# MAXIM-ADC3.net
KiCad netlist of a schematic drawn in Altium Designer
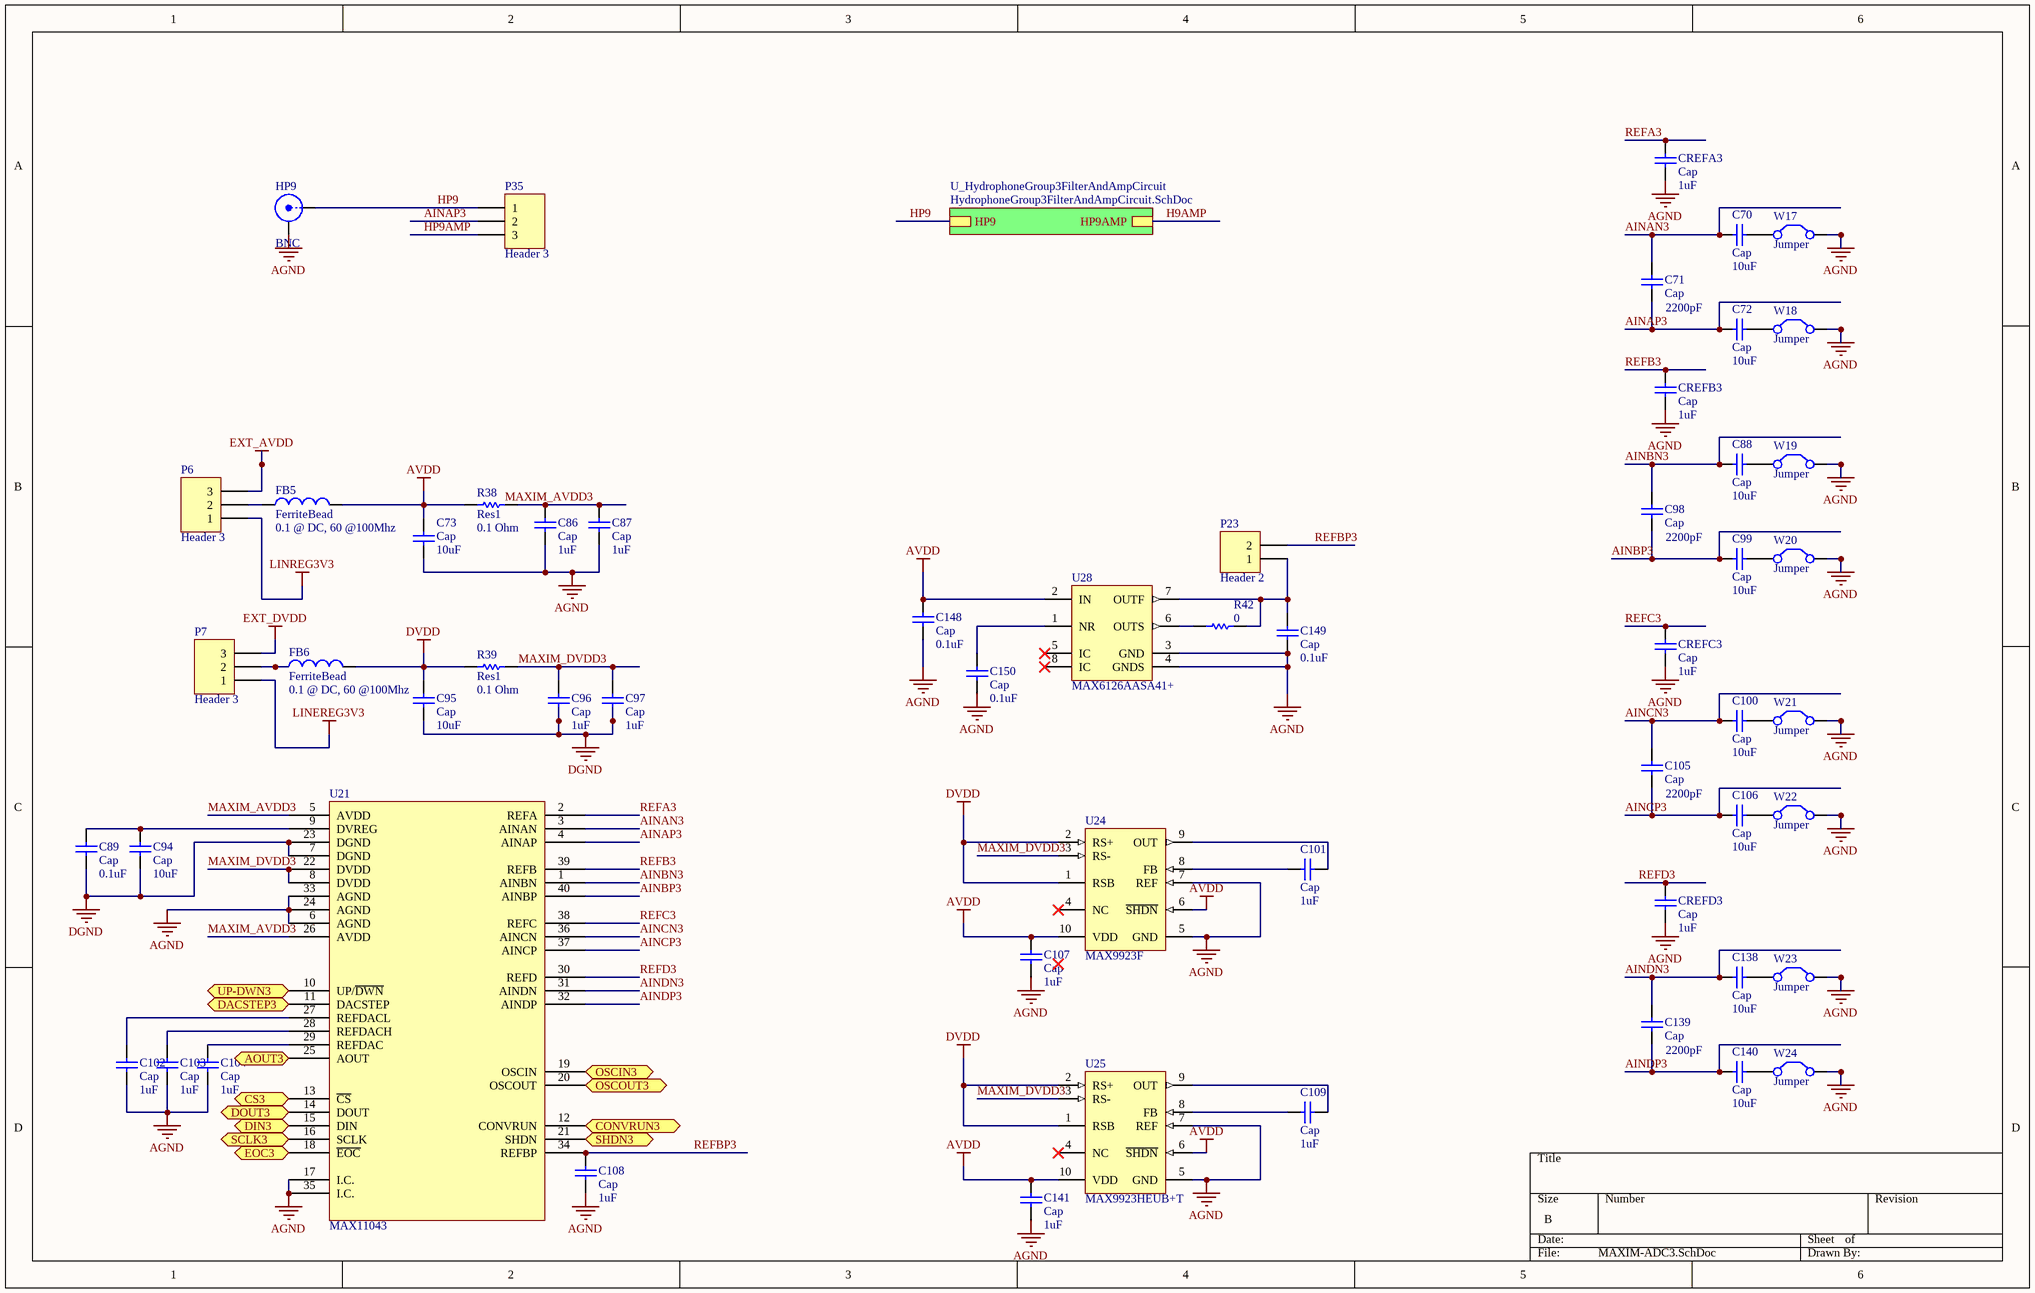
[diagram p0: MAXIM-ADC3.SchDoc]

(export (version "E")
  (design (tool "Eeschema 10.0.6"))
  (components
    (comp (ref "C70")
      (value "Cap")
      (footprint "RAD-0.3")
      (description "Capacitor")
      (fields (field (name "ALTIUM_VALUE") "10uF") (field (name "PUBLISHER") "Altium Limited"))
      (libsource (lib "Miscellaneous Devices") (part "Cap"))
    )
    (comp (ref "C71")
      (value "Cap")
      (footprint "RAD-0.3")
      (description "Capacitor")
      (fields (field (name "ALTIUM_VALUE") "2200pF") (field (name "PUBLISHER") "Altium Limited"))
      (libsource (lib "Miscellaneous Devices") (part "Cap"))
    )
    (comp (ref "C72")
      (value "Cap")
      (footprint "RAD-0.3")
      (description "Capacitor")
      (fields (field (name "ALTIUM_VALUE") "10uF") (field (name "PUBLISHER") "Altium Limited"))
      (libsource (lib "Miscellaneous Devices") (part "Cap"))
    )
    (comp (ref "C73")
      (value "Cap")
      (footprint "RAD-0.3")
      (description "Capacitor")
      (fields (field (name "ALTIUM_VALUE") "10uF") (field (name "PUBLISHER") "Altium Limited"))
      (libsource (lib "Miscellaneous Devices") (part "Cap"))
    )
    (comp (ref "C86")
      (value "Cap")
      (footprint "0603")
      (description "Capacitor")
      (fields (field (name "ALTIUM_VALUE") "1uF") (field (name "PUBLISHER") "Altium Limited"))
      (libsource (lib "Miscellaneous Devices") (part "Cap"))
    )
    (comp (ref "C87")
      (value "Cap")
      (footprint "RAD-0.3")
      (description "Capacitor")
      (fields (field (name "ALTIUM_VALUE") "1uF") (field (name "PUBLISHER") "Altium Limited"))
      (libsource (lib "Miscellaneous Devices") (part "Cap"))
    )
    (comp (ref "C88")
      (value "Cap")
      (footprint "RAD-0.3")
      (description "Capacitor")
      (fields (field (name "ALTIUM_VALUE") "10uF") (field (name "PUBLISHER") "Altium Limited"))
      (libsource (lib "Miscellaneous Devices") (part "Cap"))
    )
    (comp (ref "C89")
      (value "Cap")
      (footprint "RAD-0.3")
      (description "Capacitor")
      (fields (field (name "ALTIUM_VALUE") "0.1uF") (field (name "PUBLISHER") "Altium Limited"))
      (libsource (lib "Miscellaneous Devices") (part "Cap"))
    )
    (comp (ref "C94")
      (value "Cap")
      (footprint "RAD-0.3")
      (description "Capacitor")
      (fields (field (name "ALTIUM_VALUE") "10uF") (field (name "PUBLISHER") "Altium Limited"))
      (libsource (lib "Miscellaneous Devices") (part "Cap"))
    )
    (comp (ref "C95")
      (value "Cap")
      (footprint "RAD-0.3")
      (description "Capacitor")
      (fields (field (name "ALTIUM_VALUE") "10uF") (field (name "PUBLISHER") "Altium Limited"))
      (libsource (lib "Miscellaneous Devices") (part "Cap"))
    )
    (comp (ref "C96")
      (value "Cap")
      (footprint "RAD-0.3")
      (description "Capacitor")
      (fields (field (name "ALTIUM_VALUE") "1uF") (field (name "PUBLISHER") "Altium Limited"))
      (libsource (lib "Miscellaneous Devices") (part "Cap"))
    )
    (comp (ref "C97")
      (value "Cap")
      (footprint "RAD-0.3")
      (description "Capacitor")
      (fields (field (name "ALTIUM_VALUE") "1uF") (field (name "PUBLISHER") "Altium Limited"))
      (libsource (lib "Miscellaneous Devices") (part "Cap"))
    )
    (comp (ref "C98")
      (value "Cap")
      (footprint "RAD-0.3")
      (description "Capacitor")
      (fields (field (name "ALTIUM_VALUE") "2200pF") (field (name "PUBLISHER") "Altium Limited"))
      (libsource (lib "Miscellaneous Devices") (part "Cap"))
    )
    (comp (ref "C99")
      (value "Cap")
      (footprint "RAD-0.3")
      (description "Capacitor")
      (fields (field (name "ALTIUM_VALUE") "10uF") (field (name "PUBLISHER") "Altium Limited"))
      (libsource (lib "Miscellaneous Devices") (part "Cap"))
    )
    (comp (ref "C100")
      (value "Cap")
      (footprint "RAD-0.3")
      (description "Capacitor")
      (fields (field (name "ALTIUM_VALUE") "10uF") (field (name "PUBLISHER") "Altium Limited"))
      (libsource (lib "Miscellaneous Devices") (part "Cap"))
    )
    (comp (ref "C101")
      (value "Cap")
      (footprint "RAD-0.3")
      (description "Capacitor")
      (fields (field (name "ALTIUM_VALUE") "1uF") (field (name "PUBLISHER") "Altium Limited"))
      (libsource (lib "Miscellaneous Devices") (part "Cap"))
    )
    (comp (ref "C102")
      (value "Cap")
      (footprint "RAD-0.3")
      (description "Capacitor")
      (fields (field (name "ALTIUM_VALUE") "1uF") (field (name "PUBLISHER") "Altium Limited"))
      (libsource (lib "Miscellaneous Devices") (part "Cap"))
    )
    (comp (ref "C103")
      (value "Cap")
      (footprint "RAD-0.3")
      (description "Capacitor")
      (fields (field (name "ALTIUM_VALUE") "1uF") (field (name "PUBLISHER") "Altium Limited"))
      (libsource (lib "Miscellaneous Devices") (part "Cap"))
    )
    (comp (ref "C104")
      (value "Cap")
      (footprint "RAD-0.3")
      (description "Capacitor")
      (fields (field (name "ALTIUM_VALUE") "1uF") (field (name "PUBLISHER") "Altium Limited"))
      (libsource (lib "Miscellaneous Devices") (part "Cap"))
    )
    (comp (ref "C105")
      (value "Cap")
      (footprint "RAD-0.3")
      (description "Capacitor")
      (fields (field (name "ALTIUM_VALUE") "2200pF") (field (name "PUBLISHER") "Altium Limited"))
      (libsource (lib "Miscellaneous Devices") (part "Cap"))
    )
    (comp (ref "C106")
      (value "Cap")
      (footprint "RAD-0.3")
      (description "Capacitor")
      (fields (field (name "ALTIUM_VALUE") "10uF") (field (name "PUBLISHER") "Altium Limited"))
      (libsource (lib "Miscellaneous Devices") (part "Cap"))
    )
    (comp (ref "C107")
      (value "Cap")
      (footprint "RAD-0.3")
      (description "Capacitor")
      (fields (field (name "ALTIUM_VALUE") "1uF") (field (name "PUBLISHER") "Altium Limited"))
      (libsource (lib "Miscellaneous Devices") (part "Cap"))
    )
    (comp (ref "C108")
      (value "Cap")
      (footprint "RAD-0.3")
      (description "Capacitor")
      (fields (field (name "ALTIUM_VALUE") "1uF") (field (name "PUBLISHER") "Altium Limited"))
      (libsource (lib "Miscellaneous Devices") (part "Cap"))
    )
    (comp (ref "C109")
      (value "Cap")
      (footprint "RAD-0.3")
      (description "Capacitor")
      (fields (field (name "ALTIUM_VALUE") "1uF") (field (name "PUBLISHER") "Altium Limited"))
      (libsource (lib "Miscellaneous Devices") (part "Cap"))
    )
    (comp (ref "C138")
      (value "Cap")
      (footprint "RAD-0.3")
      (description "Capacitor")
      (fields (field (name "ALTIUM_VALUE") "10uF") (field (name "PUBLISHER") "Altium Limited"))
      (libsource (lib "Miscellaneous Devices") (part "Cap"))
    )
    (comp (ref "C139")
      (value "Cap")
      (footprint "RAD-0.3")
      (description "Capacitor")
      (fields (field (name "ALTIUM_VALUE") "2200pF") (field (name "PUBLISHER") "Altium Limited"))
      (libsource (lib "Miscellaneous Devices") (part "Cap"))
    )
    (comp (ref "C140")
      (value "Cap")
      (footprint "RAD-0.3")
      (description "Capacitor")
      (fields (field (name "ALTIUM_VALUE") "10uF") (field (name "PUBLISHER") "Altium Limited"))
      (libsource (lib "Miscellaneous Devices") (part "Cap"))
    )
    (comp (ref "C141")
      (value "Cap")
      (footprint "RAD-0.3")
      (description "Capacitor")
      (fields (field (name "ALTIUM_VALUE") "1uF") (field (name "PUBLISHER") "Altium Limited"))
      (libsource (lib "Miscellaneous Devices") (part "Cap"))
    )
    (comp (ref "C148")
      (value "Cap")
      (footprint "RAD-0.3")
      (description "Capacitor")
      (fields (field (name "ALTIUM_VALUE") "0.1uF") (field (name "PUBLISHER") "Altium Limited"))
      (libsource (lib "Miscellaneous Devices") (part "Cap"))
    )
    (comp (ref "C149")
      (value "Cap")
      (footprint "RAD-0.3")
      (description "Capacitor")
      (fields (field (name "ALTIUM_VALUE") "0.1uF") (field (name "PUBLISHER") "Altium Limited"))
      (libsource (lib "Miscellaneous Devices") (part "Cap"))
    )
    (comp (ref "C150")
      (value "Cap")
      (footprint "RAD-0.3")
      (description "Capacitor")
      (fields (field (name "ALTIUM_VALUE") "0.1uF") (field (name "PUBLISHER") "Altium Limited"))
      (libsource (lib "Miscellaneous Devices") (part "Cap"))
    )
    (comp (ref "CREFA3")
      (value "Cap")
      (footprint "RAD-0.3")
      (description "Capacitor")
      (fields (field (name "ALTIUM_VALUE") "1uF") (field (name "PUBLISHER") "Altium Limited"))
      (libsource (lib "Miscellaneous Devices") (part "Cap"))
    )
    (comp (ref "CREFB3")
      (value "Cap")
      (footprint "RAD-0.3")
      (description "Capacitor")
      (fields (field (name "ALTIUM_VALUE") "1uF") (field (name "PUBLISHER") "Altium Limited"))
      (libsource (lib "Miscellaneous Devices") (part "Cap"))
    )
    (comp (ref "CREFC3")
      (value "Cap")
      (footprint "RAD-0.3")
      (description "Capacitor")
      (fields (field (name "ALTIUM_VALUE") "1uF") (field (name "PUBLISHER") "Altium Limited"))
      (libsource (lib "Miscellaneous Devices") (part "Cap"))
    )
    (comp (ref "CREFD3")
      (value "Cap")
      (footprint "RAD-0.3")
      (description "Capacitor")
      (fields (field (name "ALTIUM_VALUE") "1uF") (field (name "PUBLISHER") "Altium Limited"))
      (libsource (lib "Miscellaneous Devices") (part "Cap"))
    )
    (comp (ref "FB5")
      (value "FerriteBead")
      (footprint "0603")
      (description "Inductor")
      (fields
        (field (name "ALTIUM_VALUE") "0.1 @ DC, 60 @100Mhz")
        (field (name "PUBLISHER") "Altium Limited")
      )
      (libsource (lib "Miscellaneous Devices") (part "Inductor"))
    )
    (comp (ref "FB6")
      (value "FerriteBead")
      (footprint "0603")
      (description "Inductor")
      (fields
        (field (name "ALTIUM_VALUE") "0.1 @ DC, 60 @100Mhz")
        (field (name "PUBLISHER") "Altium Limited")
      )
      (libsource (lib "Miscellaneous Devices") (part "Inductor"))
    )
    (comp (ref "HP9")
      (value "BNC")
      (footprint "BNC_RA CON")
      (description "BNC Elbow Connector")
      (fields (field (name "PUBLISHER") "Altium Limited"))
      (libsource (lib "Miscellaneous Connectors") (part "BNC"))
    )
    (comp (ref "P6")
      (value "Header 3")
      (footprint "HDR1X3")
      (description "Header, 3-Pin")
      (fields (field (name "PUBLISHER") "Altium Limited"))
      (libsource (lib "") (part "Header 3_1"))
    )
    (comp (ref "P7")
      (value "Header 3")
      (footprint "HDR1X3")
      (description "Header, 3-Pin")
      (fields (field (name "PUBLISHER") "Altium Limited"))
      (libsource (lib "") (part "Header 3_1"))
    )
    (comp (ref "P23")
      (value "Header 2")
      (footprint "HDR1X2")
      (description "Header, 2-Pin")
      (fields (field (name "PUBLISHER") "Altium Limited"))
      (libsource (lib "Miscellaneous Connectors") (part "Header 2"))
    )
    (comp (ref "P35")
      (value "Header 3")
      (footprint "HDR1X3")
      (description "Header, 3-Pin")
      (fields (field (name "PUBLISHER") "Altium Limited"))
      (libsource (lib "Miscellaneous Connectors") (part "Header 3"))
    )
    (comp (ref "R38")
      (value "Res1")
      (footprint "AXIAL-0.3")
      (description "Resistor")
      (fields (field (name "ALTIUM_VALUE") "0.1 Ohm") (field (name "PUBLISHER") "Altium Limited"))
      (libsource (lib "Miscellaneous Devices") (part "Res1"))
    )
    (comp (ref "R39")
      (value "Res1")
      (footprint "AXIAL-0.3")
      (description "Resistor")
      (fields (field (name "ALTIUM_VALUE") "0.1 Ohm") (field (name "PUBLISHER") "Altium Limited"))
      (libsource (lib "Miscellaneous Devices") (part "Res1"))
    )
    (comp (ref "R42")
      (value "0")
      (footprint "AXIAL-0.3")
      (description "Resistor")
      (fields (field (name "PUBLISHER") "Altium Limited"))
      (libsource (lib "Miscellaneous Devices") (part "Res1"))
    )
    (comp (ref "U21") (value "MAX11043") (libsource (lib "Max11043") (part "MAX11043")))
    (comp (ref "U24")
      (value "MAX9923F")
      (footprint "MAXM-U10+2_N")
      (fields (field (name "PARTNUMBER") "MAX9923HEUB+T"))
      (libsource (lib "Altium Content Vault") (part "MAX992X-U10+2"))
    )
    (comp (ref "U25")
      (value "MAX9923HEUB+T")
      (footprint "MAXM-U10+2_N")
      (libsource (lib "Altium Content Vault") (part "MAX992X-U10+2"))
    )
    (comp (ref "U28")
      (value "MAX6126AASA41+")
      (footprint "MAXM-S8+4_M")
      (fields (field (name "MANUFACTURER") "Maxim"))
      (libsource (lib "Altium Content Vault") (part "MAXM-MAX6126-8"))
    )
    (comp (ref "W17")
      (value "Jumper")
      (footprint "RAD-0.2")
      (description "Jumper Wire")
      (fields (field (name "PUBLISHER") "Altium Limited"))
      (libsource (lib "Miscellaneous Devices") (part "Jumper"))
    )
    (comp (ref "W18")
      (value "Jumper")
      (footprint "RAD-0.2")
      (description "Jumper Wire")
      (fields (field (name "PUBLISHER") "Altium Limited"))
      (libsource (lib "Miscellaneous Devices") (part "Jumper"))
    )
    (comp (ref "W19")
      (value "Jumper")
      (footprint "RAD-0.2")
      (description "Jumper Wire")
      (fields (field (name "PUBLISHER") "Altium Limited"))
      (libsource (lib "Miscellaneous Devices") (part "Jumper"))
    )
    (comp (ref "W20")
      (value "Jumper")
      (footprint "RAD-0.2")
      (description "Jumper Wire")
      (fields (field (name "PUBLISHER") "Altium Limited"))
      (libsource (lib "Miscellaneous Devices") (part "Jumper"))
    )
    (comp (ref "W21")
      (value "Jumper")
      (footprint "RAD-0.2")
      (description "Jumper Wire")
      (fields (field (name "PUBLISHER") "Altium Limited"))
      (libsource (lib "Miscellaneous Devices") (part "Jumper"))
    )
    (comp (ref "W22")
      (value "Jumper")
      (footprint "RAD-0.2")
      (description "Jumper Wire")
      (fields (field (name "PUBLISHER") "Altium Limited"))
      (libsource (lib "Miscellaneous Devices") (part "Jumper"))
    )
    (comp (ref "W23")
      (value "Jumper")
      (footprint "RAD-0.2")
      (description "Jumper Wire")
      (fields (field (name "PUBLISHER") "Altium Limited"))
      (libsource (lib "Miscellaneous Devices") (part "Jumper"))
    )
    (comp (ref "W24")
      (value "Jumper")
      (footprint "RAD-0.2")
      (description "Jumper Wire")
      (fields (field (name "PUBLISHER") "Altium Limited"))
      (libsource (lib "Miscellaneous Devices") (part "Jumper"))
    )
  )
  (nets
    (net (code "1") (name "/AINAN3") (class "Default")
      (node (ref "C70") (pin "2") (pinfunction "2_2") (pintype "passive"))
      (node (ref "C71") (pin "2") (pinfunction "2_2") (pintype "passive"))
      (node (ref "U21") (pin "3") (pinfunction "AINAN_3") (pintype "passive"))
    )
    (net (code "2") (name "/AINAP3") (class "Default")
      (node (ref "C71") (pin "1") (pinfunction "1_1") (pintype "passive"))
      (node (ref "C72") (pin "2") (pinfunction "2_2") (pintype "passive"))
      (node (ref "P35") (pin "2") (pinfunction "2_2") (pintype "passive"))
      (node (ref "U21") (pin "4") (pinfunction "AINAP_4") (pintype "passive"))
    )
    (net (code "3") (name "/AINBN3") (class "Default")
      (node (ref "C88") (pin "2") (pinfunction "2_2") (pintype "passive"))
      (node (ref "C98") (pin "2") (pinfunction "2_2") (pintype "passive"))
      (node (ref "U21") (pin "1") (pinfunction "AINBN_1") (pintype "passive"))
    )
    (net (code "4") (name "/AINBP3") (class "Default")
      (node (ref "C98") (pin "1") (pinfunction "1_1") (pintype "passive"))
      (node (ref "C99") (pin "2") (pinfunction "2_2") (pintype "passive"))
      (node (ref "U21") (pin "40") (pinfunction "AINBP_40") (pintype "passive"))
    )
    (net (code "5") (name "/AINCN3") (class "Default")
      (node (ref "C100") (pin "2") (pinfunction "2_2") (pintype "passive"))
      (node (ref "C105") (pin "2") (pinfunction "2_2") (pintype "passive"))
      (node (ref "U21") (pin "36") (pinfunction "AINCN_36") (pintype "passive"))
    )
    (net (code "6") (name "/AINCP3") (class "Default")
      (node (ref "C105") (pin "1") (pinfunction "1_1") (pintype "passive"))
      (node (ref "C106") (pin "2") (pinfunction "2_2") (pintype "passive"))
      (node (ref "U21") (pin "37") (pinfunction "AINCP_37") (pintype "passive"))
    )
    (net (code "7") (name "/AINDN3") (class "Default")
      (node (ref "C138") (pin "2") (pinfunction "2_2") (pintype "passive"))
      (node (ref "C139") (pin "2") (pinfunction "2_2") (pintype "passive"))
      (node (ref "U21") (pin "31") (pinfunction "AINDN_31") (pintype "passive"))
    )
    (net (code "8") (name "/AINDP3") (class "Default")
      (node (ref "C139") (pin "1") (pinfunction "1_1") (pintype "passive"))
      (node (ref "C140") (pin "2") (pinfunction "2_2") (pintype "passive"))
      (node (ref "U21") (pin "32") (pinfunction "AINDP_32") (pintype "passive"))
    )
    (net (code "9") (name "/AOUT3") (class "Default")
      (node (ref "U21") (pin "25") (pinfunction "AOUT_25") (pintype "passive"))
    )
    (net (code "10") (name "/CONVRUN3") (class "Default")
      (node (ref "U21") (pin "12") (pinfunction "CONVRUN_12") (pintype "passive"))
    )
    (net (code "11") (name "/CS3") (class "Default")
      (node (ref "U21") (pin "13") (pinfunction "~{CS}_13") (pintype "passive"))
    )
    (net (code "12") (name "/DACSTEP3") (class "Default")
      (node (ref "U21") (pin "11") (pinfunction "DACSTEP_11") (pintype "passive"))
    )
    (net (code "13") (name "/DIN3") (class "Default")
      (node (ref "U21") (pin "15") (pinfunction "DIN_15") (pintype "passive"))
    )
    (net (code "14") (name "/DOUT3") (class "Default")
      (node (ref "U21") (pin "14") (pinfunction "DOUT_14") (pintype "passive"))
    )
    (net (code "15") (name "/EOC3") (class "Default")
      (node (ref "U21") (pin "18") (pinfunction "~{EOC}_18") (pintype "passive"))
    )
    (net (code "17") (name "/HP9") (class "Default")
      (node (ref "HP9") (pin "1") (pinfunction "X_1") (pintype "passive"))
      (node (ref "P35") (pin "1") (pinfunction "1_1") (pintype "passive"))
    )
    (net (code "18") (name "/HP9AMP") (class "Default")
      (node (ref "P35") (pin "3") (pinfunction "3_3") (pintype "passive"))
    )
    (net (code "19") (name "/MAXIM_AVDD3") (class "Default")
      (node (ref "U21") (pin "26") (pinfunction "AVDD_26") (pintype "passive"))
      (node (ref "U21") (pin "5") (pinfunction "AVDD_5") (pintype "passive"))
    )
    (net (code "20") (name "/MAXIM_DVDD3") (class "Default")
      (node (ref "C96") (pin "1") (pinfunction "1_1") (pintype "passive"))
      (node (ref "C97") (pin "1") (pinfunction "1_1") (pintype "passive"))
      (node (ref "R39") (pin "1") (pinfunction "1_1") (pintype "passive"))
      (node (ref "U21") (pin "22") (pinfunction "DVDD_22") (pintype "passive"))
      (node (ref "U21") (pin "8") (pinfunction "DVDD_8") (pintype "passive"))
      (node (ref "U24") (pin "3") (pinfunction "RS-_3") (pintype "input"))
      (node (ref "U25") (pin "3") (pinfunction "RS-_3") (pintype "input"))
    )
    (net (code "21") (name "/OSCIN3") (class "Default")
      (node (ref "U21") (pin "19") (pinfunction "OSCIN_19") (pintype "passive"))
    )
    (net (code "22") (name "/OSCOUT3") (class "Default")
      (node (ref "U21") (pin "20") (pinfunction "OSCOUT_20") (pintype "passive"))
    )
    (net (code "23") (name "/REFA3") (class "Default")
      (node (ref "CREFA3") (pin "2") (pinfunction "2_2") (pintype "passive"))
      (node (ref "U21") (pin "2") (pinfunction "REFA_2") (pintype "passive"))
    )
    (net (code "24") (name "/REFB3") (class "Default")
      (node (ref "CREFB3") (pin "2") (pinfunction "2_2") (pintype "passive"))
      (node (ref "U21") (pin "39") (pinfunction "REFB_39") (pintype "passive"))
    )
    (net (code "25") (name "/REFBP3") (class "Default")
      (node (ref "C108") (pin "1") (pinfunction "1_1") (pintype "passive"))
      (node (ref "P23") (pin "2") (pinfunction "2_2") (pintype "passive"))
      (node (ref "U21") (pin "34") (pinfunction "REFBP_34") (pintype "passive"))
    )
    (net (code "26") (name "/REFC3") (class "Default")
      (node (ref "CREFC3") (pin "2") (pinfunction "2_2") (pintype "passive"))
      (node (ref "U21") (pin "38") (pinfunction "REFC_38") (pintype "passive"))
    )
    (net (code "27") (name "/REFD3") (class "Default")
      (node (ref "CREFD3") (pin "2") (pinfunction "2_2") (pintype "passive"))
      (node (ref "U21") (pin "30") (pinfunction "REFD_30") (pintype "passive"))
    )
    (net (code "28") (name "/SCLK3") (class "Default")
      (node (ref "U21") (pin "16") (pinfunction "SCLK_16") (pintype "passive"))
    )
    (net (code "29") (name "/SHDN3") (class "Default")
      (node (ref "U21") (pin "21") (pinfunction "SHDN_21") (pintype "passive"))
    )
    (net (code "30") (name "/UP-DWN3") (class "Default")
      (node (ref "U21") (pin "10") (pinfunction "UP/~{DWN}_10") (pintype "passive"))
    )
    (net (code "31") (name "AGND") (class "Default")
      (node (ref "C102") (pin "1") (pinfunction "1_1") (pintype "passive"))
      (node (ref "C103") (pin "2") (pinfunction "2_2") (pintype "passive"))
      (node (ref "C104") (pin "1") (pinfunction "1_1") (pintype "passive"))
      (node (ref "C107") (pin "1") (pinfunction "1_1") (pintype "passive"))
      (node (ref "C108") (pin "2") (pinfunction "2_2") (pintype "passive"))
      (node (ref "C141") (pin "1") (pinfunction "1_1") (pintype "passive"))
      (node (ref "C148") (pin "2") (pinfunction "2_2") (pintype "passive"))
      (node (ref "C149") (pin "2") (pinfunction "2_2") (pintype "passive"))
      (node (ref "C150") (pin "2") (pinfunction "2_2") (pintype "passive"))
      (node (ref "C73") (pin "2") (pinfunction "2_2") (pintype "passive"))
      (node (ref "C86") (pin "2") (pinfunction "2_2") (pintype "passive"))
      (node (ref "C87") (pin "2") (pinfunction "2_2") (pintype "passive"))
      (node (ref "CREFA3") (pin "1") (pinfunction "1_1") (pintype "passive"))
      (node (ref "CREFB3") (pin "1") (pinfunction "1_1") (pintype "passive"))
      (node (ref "CREFC3") (pin "1") (pinfunction "1_1") (pintype "passive"))
      (node (ref "CREFD3") (pin "1") (pinfunction "1_1") (pintype "passive"))
      (node (ref "HP9") (pin "2") (pinfunction "Y_2") (pintype "passive"))
      (node (ref "U21") (pin "17") (pinfunction "I.C._17") (pintype "passive"))
      (node (ref "U21") (pin "24") (pinfunction "AGND_24") (pintype "passive"))
      (node (ref "U21") (pin "33") (pinfunction "AGND_33") (pintype "passive"))
      (node (ref "U21") (pin "35") (pinfunction "I.C._35") (pintype "passive"))
      (node (ref "U21") (pin "6") (pinfunction "AGND_6") (pintype "passive"))
      (node (ref "U24") (pin "5") (pinfunction "GND_5") (pintype "power_in"))
      (node (ref "U24") (pin "7") (pinfunction "REF_7") (pintype "input"))
      (node (ref "U25") (pin "5") (pinfunction "GND_5") (pintype "power_in"))
      (node (ref "U25") (pin "7") (pinfunction "REF_7") (pintype "input"))
      (node (ref "U28") (pin "3") (pinfunction "GND_3") (pintype "power_in"))
      (node (ref "U28") (pin "4") (pinfunction "GNDS_4") (pintype "power_in"))
      (node (ref "W17") (pin "2") (pinfunction "C2_2") (pintype "passive"))
      (node (ref "W18") (pin "2") (pinfunction "C2_2") (pintype "passive"))
      (node (ref "W19") (pin "2") (pinfunction "C2_2") (pintype "passive"))
      (node (ref "W20") (pin "2") (pinfunction "C2_2") (pintype "passive"))
      (node (ref "W21") (pin "2") (pinfunction "C2_2") (pintype "passive"))
      (node (ref "W22") (pin "2") (pinfunction "C2_2") (pintype "passive"))
      (node (ref "W23") (pin "2") (pinfunction "C2_2") (pintype "passive"))
      (node (ref "W24") (pin "2") (pinfunction "C2_2") (pintype "passive"))
    )
    (net (code "32") (name "AVDD") (class "Default")
      (node (ref "C107") (pin "2") (pinfunction "2_2") (pintype "passive"))
      (node (ref "C141") (pin "2") (pinfunction "2_2") (pintype "passive"))
      (node (ref "C148") (pin "1") (pinfunction "1_1") (pintype "passive"))
      (node (ref "C73") (pin "1") (pinfunction "1_1") (pintype "passive"))
      (node (ref "FB5") (pin "2") (pinfunction "2_2") (pintype "passive"))
      (node (ref "R38") (pin "2") (pinfunction "2_2") (pintype "passive"))
      (node (ref "U24") (pin "10") (pinfunction "VDD_10") (pintype "power_in"))
      (node (ref "U24") (pin "6") (pinfunction "~{SHDN}_6") (pintype "input"))
      (node (ref "U25") (pin "10") (pinfunction "VDD_10") (pintype "power_in"))
      (node (ref "U25") (pin "6") (pinfunction "~{SHDN}_6") (pintype "input"))
      (node (ref "U28") (pin "2") (pinfunction "IN_2") (pintype "power_in"))
    )
    (net (code "33") (name "DGND") (class "Default")
      (node (ref "C89") (pin "2") (pinfunction "2_2") (pintype "passive"))
      (node (ref "C94") (pin "2") (pinfunction "2_2") (pintype "passive"))
      (node (ref "C95") (pin "2") (pinfunction "2_2") (pintype "passive"))
      (node (ref "C96") (pin "2") (pinfunction "2_2") (pintype "passive"))
      (node (ref "C97") (pin "2") (pinfunction "2_2") (pintype "passive"))
      (node (ref "U21") (pin "23") (pinfunction "DGND_23") (pintype "passive"))
      (node (ref "U21") (pin "7") (pinfunction "DGND_7") (pintype "passive"))
    )
    (net (code "34") (name "DVDD") (class "Default")
      (node (ref "C95") (pin "1") (pinfunction "1_1") (pintype "passive"))
      (node (ref "FB6") (pin "2") (pinfunction "2_2") (pintype "passive"))
      (node (ref "R39") (pin "2") (pinfunction "2_2") (pintype "passive"))
      (node (ref "U24") (pin "1") (pinfunction "RSB_1") (pintype "power_in"))
      (node (ref "U24") (pin "2") (pinfunction "RS+_2") (pintype "input"))
      (node (ref "U25") (pin "1") (pinfunction "RSB_1") (pintype "power_in"))
      (node (ref "U25") (pin "2") (pinfunction "RS+_2") (pintype "input"))
    )
    (net (code "35") (name "EXT_AVDD") (class "Default")
      (node (ref "P6") (pin "3") (pinfunction "3_3") (pintype "passive"))
    )
    (net (code "36") (name "EXT_DVDD") (class "Default")
      (node (ref "P7") (pin "3") (pinfunction "3_3") (pintype "passive"))
    )
    (net (code "37") (name "LINEREG3V3") (class "Default")
      (node (ref "P7") (pin "1") (pinfunction "1_1") (pintype "passive"))
    )
    (net (code "38") (name "LINREG3V3") (class "Default")
      (node (ref "P6") (pin "1") (pinfunction "1_1") (pintype "passive"))
    )
    (net (code "39") (name "Net-(C86-Pad1)") (class "Default")
      (node (ref "C86") (pin "1") (pinfunction "1_1") (pintype "passive"))
      (node (ref "C87") (pin "1") (pinfunction "1_1") (pintype "passive"))
      (node (ref "R38") (pin "1") (pinfunction "1_1") (pintype "passive"))
    )
    (net (code "40") (name "Net-(FB5-Pad1)") (class "Default")
      (node (ref "FB5") (pin "1") (pinfunction "1_1") (pintype "passive"))
      (node (ref "P6") (pin "2") (pinfunction "2_2") (pintype "passive"))
    )
    (net (code "41") (name "Net-(FB6-Pad1)") (class "Default")
      (node (ref "FB6") (pin "1") (pinfunction "1_1") (pintype "passive"))
      (node (ref "P7") (pin "2") (pinfunction "2_2") (pintype "passive"))
    )
    (net (code "42") (name "Net-(U21-DVREG)") (class "Default")
      (node (ref "C89") (pin "1") (pinfunction "1_1") (pintype "passive"))
      (node (ref "C94") (pin "1") (pinfunction "1_1") (pintype "passive"))
      (node (ref "U21") (pin "9") (pinfunction "DVREG_9") (pintype "passive"))
    )
    (net (code "43") (name "Net-(U21-REFDAC)") (class "Default")
      (node (ref "C104") (pin "2") (pinfunction "2_2") (pintype "passive"))
      (node (ref "U21") (pin "29") (pinfunction "REFDAC_29") (pintype "passive"))
    )
    (net (code "44") (name "Net-(U21-REFDACH)") (class "Default")
      (node (ref "C103") (pin "1") (pinfunction "1_1") (pintype "passive"))
      (node (ref "U21") (pin "28") (pinfunction "REFDACH_28") (pintype "passive"))
    )
    (net (code "45") (name "Net-(U21-REFDACL)") (class "Default")
      (node (ref "C102") (pin "2") (pinfunction "2_2") (pintype "passive"))
      (node (ref "U21") (pin "27") (pinfunction "REFDACL_27") (pintype "passive"))
    )
    (net (code "46") (name "Net-(U24-FB)") (class "Default")
      (node (ref "C101") (pin "1") (pinfunction "1_1") (pintype "passive"))
      (node (ref "U24") (pin "8") (pinfunction "FB_8") (pintype "input"))
    )
    (net (code "47") (name "Net-(U24-OUT)") (class "Default")
      (node (ref "C101") (pin "2") (pinfunction "2_2") (pintype "passive"))
      (node (ref "U24") (pin "9") (pinfunction "OUT_9") (pintype "output"))
    )
    (net (code "48") (name "Net-(U25-FB)") (class "Default")
      (node (ref "C109") (pin "1") (pinfunction "1_1") (pintype "passive"))
      (node (ref "U25") (pin "8") (pinfunction "FB_8") (pintype "input"))
    )
    (net (code "49") (name "Net-(U25-OUT)") (class "Default")
      (node (ref "C109") (pin "2") (pinfunction "2_2") (pintype "passive"))
      (node (ref "U25") (pin "9") (pinfunction "OUT_9") (pintype "output"))
    )
    (net (code "50") (name "Net-(U28-NR)") (class "Default")
      (node (ref "C150") (pin "1") (pinfunction "1_1") (pintype "passive"))
      (node (ref "U28") (pin "1") (pinfunction "NR_1") (pintype "passive"))
    )
    (net (code "51") (name "Net-(U28-OUTF)") (class "Default")
      (node (ref "C149") (pin "1") (pinfunction "1_1") (pintype "passive"))
      (node (ref "P23") (pin "1") (pinfunction "1_1") (pintype "passive"))
      (node (ref "R42") (pin "1") (pinfunction "1_1") (pintype "passive"))
      (node (ref "U28") (pin "7") (pinfunction "OUTF_7") (pintype "output"))
    )
    (net (code "52") (name "Net-(U28-OUTS)") (class "Default")
      (node (ref "R42") (pin "2") (pinfunction "2_2") (pintype "passive"))
      (node (ref "U28") (pin "6") (pinfunction "OUTS_6") (pintype "output"))
    )
    (net (code "53") (name "Net-(W17-C1)") (class "Default")
      (node (ref "C70") (pin "1") (pinfunction "1_1") (pintype "passive"))
      (node (ref "W17") (pin "1") (pinfunction "C1_1") (pintype "passive"))
    )
    (net (code "54") (name "Net-(W18-C1)") (class "Default")
      (node (ref "C72") (pin "1") (pinfunction "1_1") (pintype "passive"))
      (node (ref "W18") (pin "1") (pinfunction "C1_1") (pintype "passive"))
    )
    (net (code "55") (name "Net-(W19-C1)") (class "Default")
      (node (ref "C88") (pin "1") (pinfunction "1_1") (pintype "passive"))
      (node (ref "W19") (pin "1") (pinfunction "C1_1") (pintype "passive"))
    )
    (net (code "56") (name "Net-(W20-C1)") (class "Default")
      (node (ref "C99") (pin "1") (pinfunction "1_1") (pintype "passive"))
      (node (ref "W20") (pin "1") (pinfunction "C1_1") (pintype "passive"))
    )
    (net (code "57") (name "Net-(W21-C1)") (class "Default")
      (node (ref "C100") (pin "1") (pinfunction "1_1") (pintype "passive"))
      (node (ref "W21") (pin "1") (pinfunction "C1_1") (pintype "passive"))
    )
    (net (code "58") (name "Net-(W22-C1)") (class "Default")
      (node (ref "C106") (pin "1") (pinfunction "1_1") (pintype "passive"))
      (node (ref "W22") (pin "1") (pinfunction "C1_1") (pintype "passive"))
    )
    (net (code "59") (name "Net-(W23-C1)") (class "Default")
      (node (ref "C138") (pin "1") (pinfunction "1_1") (pintype "passive"))
      (node (ref "W23") (pin "1") (pinfunction "C1_1") (pintype "passive"))
    )
    (net (code "60") (name "Net-(W24-C1)") (class "Default")
      (node (ref "C140") (pin "1") (pinfunction "1_1") (pintype "passive"))
      (node (ref "W24") (pin "1") (pinfunction "C1_1") (pintype "passive"))
    )
    (net (code "61") (name "unconnected-(U24-NC-Pad4)") (class "Default")
      (node (ref "U24") (pin "4") (pinfunction "NC_4") (pintype "passive+no_connect"))
    )
    (net (code "62") (name "unconnected-(U25-NC-Pad4)") (class "Default")
      (node (ref "U25") (pin "4") (pinfunction "NC_4") (pintype "passive+no_connect"))
    )
    (net (code "63") (name "unconnected-(U28-IC-Pad5)") (class "Default")
      (node (ref "U28") (pin "5") (pinfunction "IC_5") (pintype "passive+no_connect"))
    )
    (net (code "64") (name "unconnected-(U28-IC-Pad8)") (class "Default")
      (node (ref "U28") (pin "8") (pinfunction "IC_8") (pintype "passive+no_connect"))
    )
  )
)
